# IMS_Baseboard.net
KiCad netlist of a schematic drawn in EasyEDA Pro
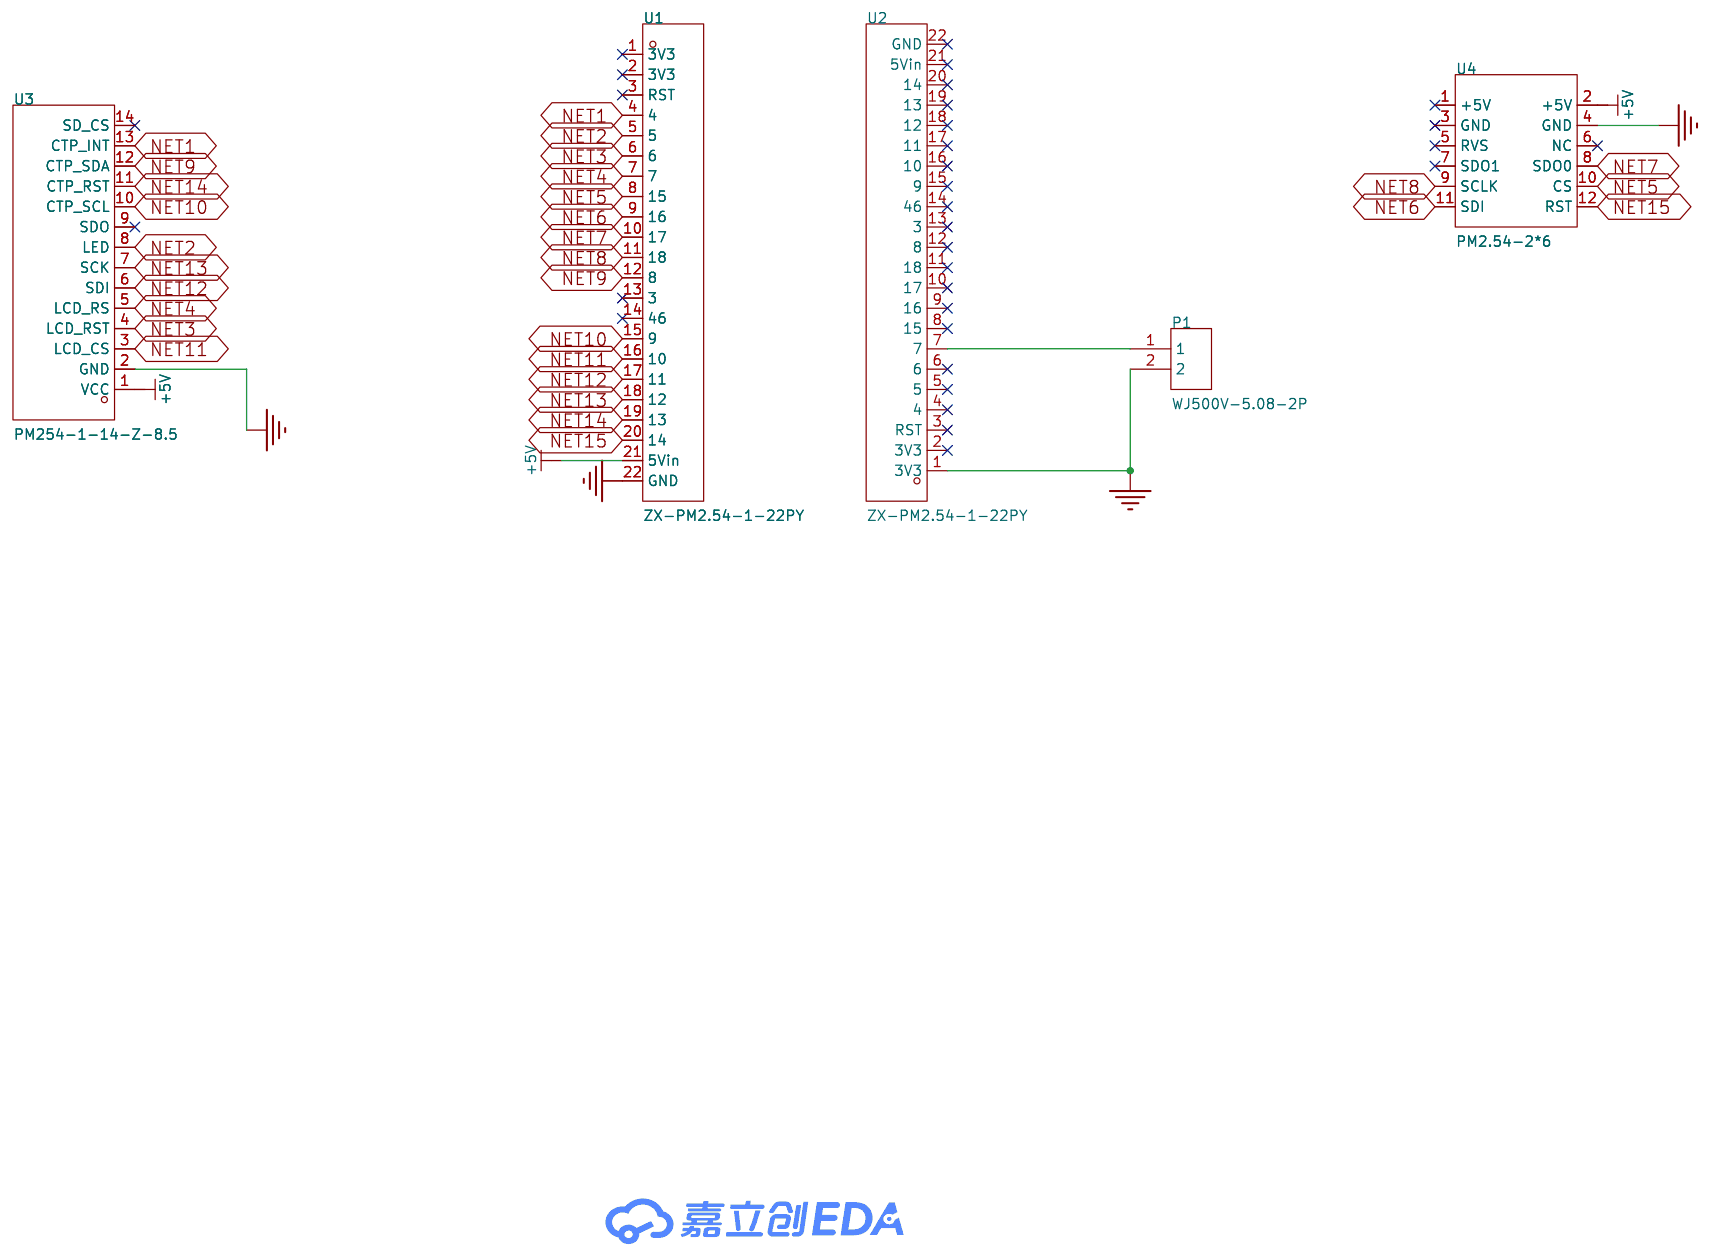
[diagram p0: schematic sheet]

(export (version "E")
  (design (tool "Eeschema 10.0.6"))
  (components
    (comp (ref "P1")
      (value "WJ500V-5.08-2P")
      (footprint "easyedapro:CONN-TH_2P-P5.00_WJ500V-5.08-2P")
      (fields (field (name "Manufacturer") "KANGNEX(康奈克斯电气)"))
      (libsource (lib "easyedapro") (part "WJ500V-5.08-2P-14-00A"))
    )
    (comp (ref "U1")
      (value "ZX-PM2.54-1-22PY")
      (footprint "easyedapro:HDR-TH_22P-P2.54-V-F")
      (fields (field (name "Manufacturer") "Megastar(兆星)"))
      (libsource (lib "easyedapro") (part "ZX-PM2.54-1-22PY"))
    )
    (comp (ref "U2")
      (value "ZX-PM2.54-1-22PY")
      (footprint "easyedapro:HDR-TH_22P-P2.54-V-F")
      (fields (field (name "Manufacturer") "Megastar(兆星)"))
      (libsource (lib "easyedapro") (part "ZX-PM2.54-1-22PY"))
    )
    (comp (ref "U3")
      (value "PM254-1-14-Z-8.5")
      (footprint "easyedapro:HDR-TH_14P-P2.54-V-F-1")
      (fields (field (name "Manufacturer") "HCTL(华灿天禄)"))
      (libsource (lib "easyedapro") (part "PM254-1-14-Z-8.5-gai"))
    )
    (comp (ref "U4")
      (value "PM2.54-2*6")
      (footprint "easyedapro:HDR-TH_12P-P2.54-V-F-R2-C6-S2.54")
      (fields (field (name "Manufacturer") "ZHOURI(洲日)"))
      (libsource (lib "easyedapro") (part "PM2.54-2*6-gai"))
    )
  )
  (nets
    (net (code "1") (name "+5V") (class "Default")
      (node (ref "U1") (pin "21") (pinfunction "5Vin_21") (pintype "unspecified"))
      (node (ref "U3") (pin "1") (pinfunction "VCC_1") (pintype "unspecified"))
      (node (ref "U4") (pin "2") (pinfunction "+5V_2") (pintype "unspecified"))
    )
    (net (code "2") (name "GND") (class "Default")
      (node (ref "U1") (pin "22") (pinfunction "GND_22") (pintype "unspecified"))
      (node (ref "U3") (pin "2") (pinfunction "GND_2") (pintype "unspecified"))
    )
    (net (code "3") (name "GND1") (class "Default")
      (node (ref "P1") (pin "2") (pinfunction "2_2") (pintype "unspecified"))
      (node (ref "U2") (pin "1") (pinfunction "3V3_1") (pintype "unspecified"))
      (node (ref "U4") (pin "4") (pinfunction "GND_4") (pintype "unspecified"))
    )
    (net (code "4") (name "NET1") (class "Default")
      (node (ref "U1") (pin "4") (pinfunction "4_4") (pintype "unspecified"))
      (node (ref "U3") (pin "13") (pinfunction "CTP_INT_13") (pintype "unspecified"))
    )
    (net (code "5") (name "NET2") (class "Default")
      (node (ref "U1") (pin "5") (pinfunction "5_5") (pintype "unspecified"))
      (node (ref "U3") (pin "8") (pinfunction "LED_8") (pintype "unspecified"))
    )
    (net (code "6") (name "NET3") (class "Default")
      (node (ref "U1") (pin "6") (pinfunction "6_6") (pintype "unspecified"))
      (node (ref "U3") (pin "4") (pinfunction "LCD_RST_4") (pintype "unspecified"))
    )
    (net (code "7") (name "NET4") (class "Default")
      (node (ref "U1") (pin "7") (pinfunction "7_7") (pintype "unspecified"))
      (node (ref "U3") (pin "5") (pinfunction "LCD_RS_5") (pintype "unspecified"))
    )
    (net (code "8") (name "NET5") (class "Default")
      (node (ref "U1") (pin "8") (pinfunction "15_8") (pintype "unspecified"))
      (node (ref "U4") (pin "10") (pinfunction "CS_10") (pintype "unspecified"))
    )
    (net (code "9") (name "NET6") (class "Default")
      (node (ref "U1") (pin "9") (pinfunction "16_9") (pintype "unspecified"))
      (node (ref "U4") (pin "11") (pinfunction "SDI_11") (pintype "unspecified"))
    )
    (net (code "10") (name "NET7") (class "Default")
      (node (ref "U1") (pin "10") (pinfunction "17_10") (pintype "unspecified"))
      (node (ref "U4") (pin "8") (pinfunction "SDO0_8") (pintype "unspecified"))
    )
    (net (code "11") (name "NET8") (class "Default")
      (node (ref "U1") (pin "11") (pinfunction "18_11") (pintype "unspecified"))
      (node (ref "U4") (pin "9") (pinfunction "SCLK_9") (pintype "unspecified"))
    )
    (net (code "12") (name "NET9") (class "Default")
      (node (ref "U1") (pin "12") (pinfunction "8_12") (pintype "unspecified"))
      (node (ref "U3") (pin "12") (pinfunction "CTP_SDA_12") (pintype "unspecified"))
    )
    (net (code "13") (name "NET10") (class "Default")
      (node (ref "U1") (pin "15") (pinfunction "9_15") (pintype "unspecified"))
      (node (ref "U3") (pin "10") (pinfunction "CTP_SCL_10") (pintype "unspecified"))
    )
    (net (code "14") (name "NET11") (class "Default")
      (node (ref "U1") (pin "16") (pinfunction "10_16") (pintype "unspecified"))
      (node (ref "U3") (pin "3") (pinfunction "LCD_CS_3") (pintype "unspecified"))
    )
    (net (code "15") (name "NET12") (class "Default")
      (node (ref "U1") (pin "17") (pinfunction "11_17") (pintype "unspecified"))
      (node (ref "U3") (pin "6") (pinfunction "SDI_6") (pintype "unspecified"))
    )
    (net (code "16") (name "NET13") (class "Default")
      (node (ref "U1") (pin "18") (pinfunction "12_18") (pintype "unspecified"))
      (node (ref "U3") (pin "7") (pinfunction "SCK_7") (pintype "unspecified"))
    )
    (net (code "17") (name "NET14") (class "Default")
      (node (ref "U1") (pin "19") (pinfunction "13_19") (pintype "unspecified"))
      (node (ref "U3") (pin "11") (pinfunction "CTP_RST_11") (pintype "unspecified"))
    )
    (net (code "18") (name "NET15") (class "Default")
      (node (ref "U1") (pin "20") (pinfunction "14_20") (pintype "unspecified"))
      (node (ref "U4") (pin "12") (pinfunction "RST_12") (pintype "unspecified"))
    )
    (net (code "19") (name "Net-(P1-Pad1)") (class "Default")
      (node (ref "P1") (pin "1") (pinfunction "1_1") (pintype "unspecified"))
      (node (ref "U2") (pin "7") (pinfunction "7_7") (pintype "unspecified"))
    )
    (net (code "20") (name "unconnected-(U1-3-Pad13)") (class "Default")
      (node (ref "U1") (pin "13") (pinfunction "3_13") (pintype "unspecified+no_connect"))
    )
    (net (code "21") (name "unconnected-(U1-3V3-Pad1)") (class "Default")
      (node (ref "U1") (pin "1") (pinfunction "3V3_1") (pintype "unspecified+no_connect"))
    )
    (net (code "22") (name "unconnected-(U1-3V3-Pad2)") (class "Default")
      (node (ref "U1") (pin "2") (pinfunction "3V3_2") (pintype "unspecified+no_connect"))
    )
    (net (code "23") (name "unconnected-(U1-46-Pad14)") (class "Default")
      (node (ref "U1") (pin "14") (pinfunction "46_14") (pintype "unspecified+no_connect"))
    )
    (net (code "24") (name "unconnected-(U1-RST-Pad3)") (class "Default")
      (node (ref "U1") (pin "3") (pinfunction "RST_3") (pintype "unspecified+no_connect"))
    )
    (net (code "25") (name "unconnected-(U2-3-Pad13)") (class "Default")
      (node (ref "U2") (pin "13") (pinfunction "3_13") (pintype "unspecified+no_connect"))
    )
    (net (code "26") (name "unconnected-(U2-3V3-Pad2)") (class "Default")
      (node (ref "U2") (pin "2") (pinfunction "3V3_2") (pintype "unspecified+no_connect"))
    )
    (net (code "27") (name "unconnected-(U2-5Vin-Pad21)") (class "Default")
      (node (ref "U2") (pin "21") (pinfunction "5Vin_21") (pintype "unspecified+no_connect"))
    )
    (net (code "28") (name "unconnected-(U2-8-Pad12)") (class "Default")
      (node (ref "U2") (pin "12") (pinfunction "8_12") (pintype "unspecified+no_connect"))
    )
    (net (code "29") (name "unconnected-(U2-9-Pad15)") (class "Default")
      (node (ref "U2") (pin "15") (pinfunction "9_15") (pintype "unspecified+no_connect"))
    )
    (net (code "30") (name "unconnected-(U2-10-Pad16)") (class "Default")
      (node (ref "U2") (pin "16") (pinfunction "10_16") (pintype "unspecified+no_connect"))
    )
    (net (code "31") (name "unconnected-(U2-11-Pad17)") (class "Default")
      (node (ref "U2") (pin "17") (pinfunction "11_17") (pintype "unspecified+no_connect"))
    )
    (net (code "32") (name "unconnected-(U2-12-Pad18)") (class "Default")
      (node (ref "U2") (pin "18") (pinfunction "12_18") (pintype "unspecified+no_connect"))
    )
    (net (code "33") (name "unconnected-(U2-13-Pad19)") (class "Default")
      (node (ref "U2") (pin "19") (pinfunction "13_19") (pintype "unspecified+no_connect"))
    )
    (net (code "34") (name "unconnected-(U2-14-Pad20)") (class "Default")
      (node (ref "U2") (pin "20") (pinfunction "14_20") (pintype "unspecified+no_connect"))
    )
    (net (code "35") (name "unconnected-(U2-15-Pad8)") (class "Default")
      (node (ref "U2") (pin "8") (pinfunction "15_8") (pintype "unspecified+no_connect"))
    )
    (net (code "36") (name "unconnected-(U2-16-Pad9)") (class "Default")
      (node (ref "U2") (pin "9") (pinfunction "16_9") (pintype "unspecified+no_connect"))
    )
    (net (code "37") (name "unconnected-(U2-17-Pad10)") (class "Default")
      (node (ref "U2") (pin "10") (pinfunction "17_10") (pintype "unspecified+no_connect"))
    )
    (net (code "38") (name "unconnected-(U2-18-Pad11)") (class "Default")
      (node (ref "U2") (pin "11") (pinfunction "18_11") (pintype "unspecified+no_connect"))
    )
    (net (code "39") (name "unconnected-(U2-46-Pad14)") (class "Default")
      (node (ref "U2") (pin "14") (pinfunction "46_14") (pintype "unspecified+no_connect"))
    )
    (net (code "40") (name "unconnected-(U2-GND-Pad22)") (class "Default")
      (node (ref "U2") (pin "22") (pinfunction "GND_22") (pintype "unspecified+no_connect"))
    )
    (net (code "41") (name "unconnected-(U2-Pad4)") (class "Default")
      (node (ref "U2") (pin "4") (pinfunction "4_4") (pintype "unspecified+no_connect"))
    )
    (net (code "42") (name "unconnected-(U2-Pad5)") (class "Default")
      (node (ref "U2") (pin "5") (pinfunction "5_5") (pintype "unspecified+no_connect"))
    )
    (net (code "43") (name "unconnected-(U2-Pad6)") (class "Default")
      (node (ref "U2") (pin "6") (pinfunction "6_6") (pintype "unspecified+no_connect"))
    )
    (net (code "44") (name "unconnected-(U2-RST-Pad3)") (class "Default")
      (node (ref "U2") (pin "3") (pinfunction "RST_3") (pintype "unspecified+no_connect"))
    )
    (net (code "45") (name "unconnected-(U3-SDO-Pad9)") (class "Default")
      (node (ref "U3") (pin "9") (pinfunction "SDO_9") (pintype "unspecified+no_connect"))
    )
    (net (code "46") (name "unconnected-(U3-SD_CS-Pad14)") (class "Default")
      (node (ref "U3") (pin "14") (pinfunction "SD_CS_14") (pintype "unspecified+no_connect"))
    )
    (net (code "47") (name "unconnected-(U4-+5V-Pad1)") (class "Default")
      (node (ref "U4") (pin "1") (pinfunction "+5V_1") (pintype "unspecified+no_connect"))
    )
    (net (code "48") (name "unconnected-(U4-GND-Pad3)") (class "Default")
      (node (ref "U4") (pin "3") (pinfunction "GND_3") (pintype "unspecified+no_connect"))
    )
    (net (code "49") (name "unconnected-(U4-NC-Pad6)") (class "Default")
      (node (ref "U4") (pin "6") (pinfunction "NC_6") (pintype "unspecified+no_connect"))
    )
    (net (code "50") (name "unconnected-(U4-RVS-Pad5)") (class "Default")
      (node (ref "U4") (pin "5") (pinfunction "RVS_5") (pintype "unspecified+no_connect"))
    )
    (net (code "51") (name "unconnected-(U4-SDO1-Pad7)") (class "Default")
      (node (ref "U4") (pin "7") (pinfunction "SDO1_7") (pintype "unspecified+no_connect"))
    )
  )
)
